# sheet0.net
KiCad netlist of a schematic drawn in Altium Designer
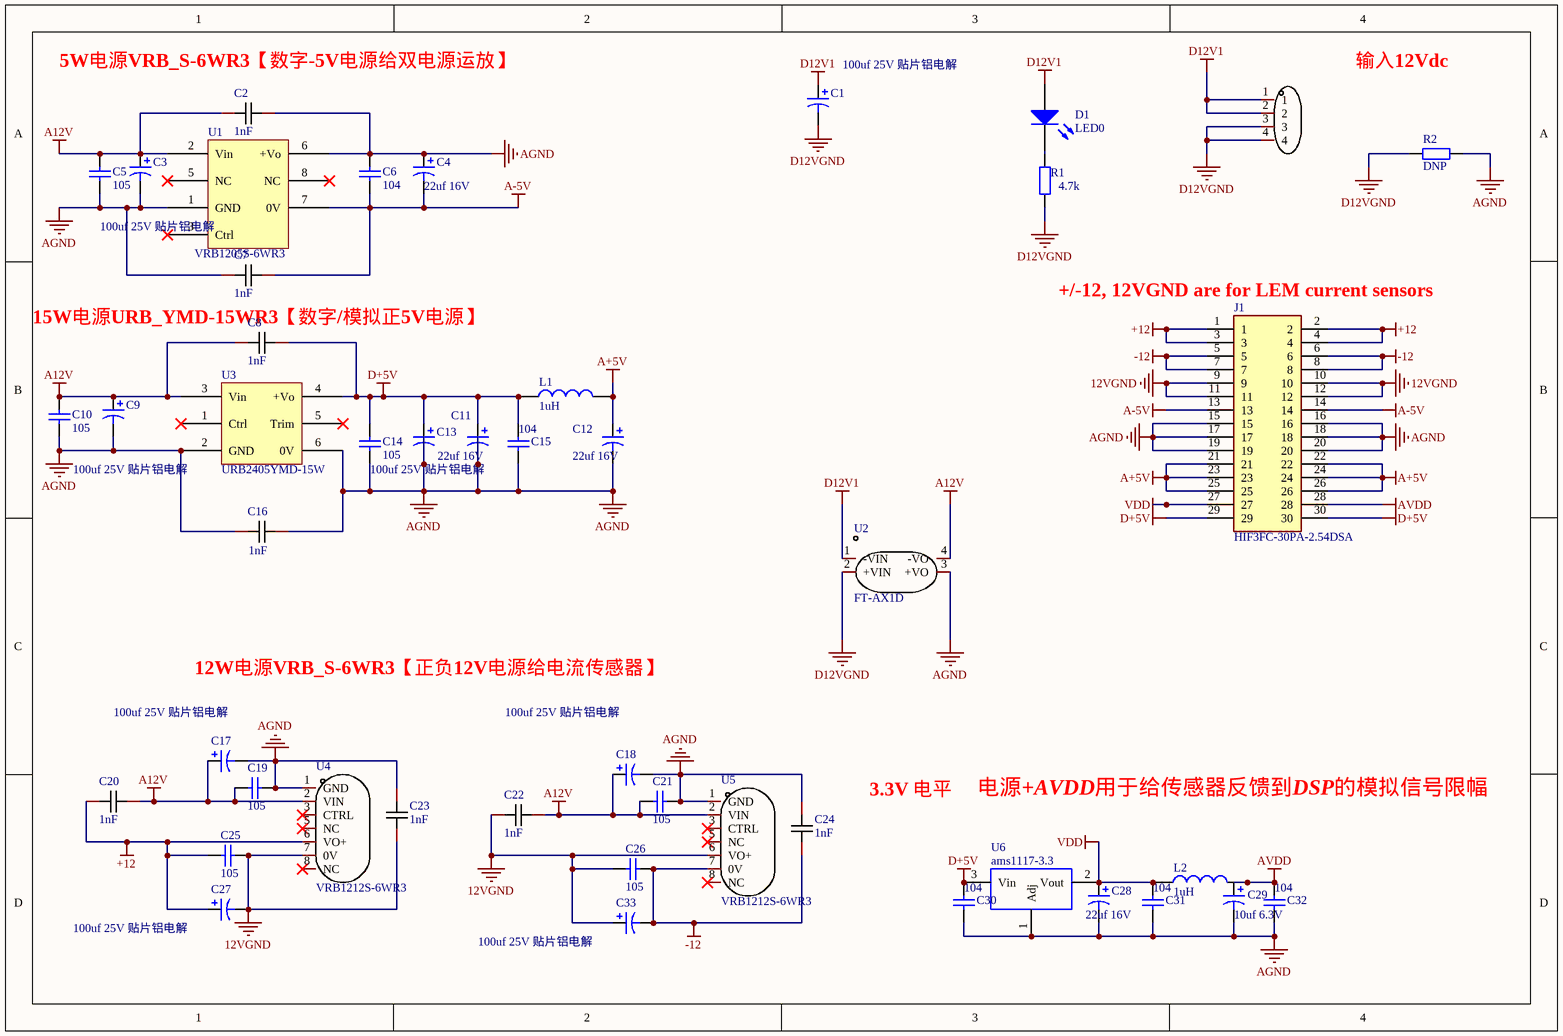
[diagram p0: sheet0.SchDoc]

(export (version "E")
  (design (tool "Eeschema 10.0.6"))
  (components
    (comp (ref "C1")
      (value "100uf 25V 贴片铝电解")
      (footprint "CAP/6.4mm -")
      (description "Polarized Capacitor (Radial)")
      (fields (field (name "PUBLISHER") "Altium Limited"))
      (libsource (lib "Miscellaneous Devices") (part "Cap Pol1"))
    )
    (comp (ref "C2")
      (value "1nF")
      (footprint "CAP-TH_L7.5-W4.5-P10.00-D0.6")
      (description "等级:Y1;容值:1nF;精度:±20%;电压(AC):400V;")
      (fields
        (field (name "MANUFACTURER") "KNSCHA(科尼盛)")
        (field (name "MANUFACTURER PART") "KY1102M400VAC70Y10093")
        (field (name "NAME") "1nF")
      )
      (libsource (lib "Power") (part "KY1102M400VAC70Y10093"))
    )
    (comp (ref "C3")
      (value "100uf 25V 贴片铝电解")
      (footprint "CAP/6.4mm -")
      (description "Polarized Capacitor (Radial)")
      (fields (field (name "PUBLISHER") "Altium Limited"))
      (libsource (lib "Miscellaneous Devices") (part "Cap Pol1"))
    )
    (comp (ref "C4")
      (value "22uf 16V")
      (footprint "Project_Oshinoko:1206 (钽电容)")
      (description "Polarized Capacitor (Radial)")
      (fields (field (name "PUBLISHER") "Altium Limited"))
      (libsource (lib "Project_Oshinoko") (part "Cap Pol1"))
    )
    (comp (ref "C5")
      (value "105")
      (footprint "Project_Oshinoko:0805")
      (description "Capacitor")
      (fields (field (name "PUBLISHER") "Altium Limited"))
      (libsource (lib "Miscellaneous Devices") (part "Cap"))
    )
    (comp (ref "C6")
      (value "104")
      (footprint "0805")
      (description "Capacitor")
      (fields (field (name "PUBLISHER") "Altium Limited"))
      (libsource (lib "Miscellaneous Devices") (part "Cap"))
    )
    (comp (ref "C7")
      (value "1nF")
      (footprint "CAP-TH_L7.5-W4.5-P10.00-D0.6")
      (description "等级:Y1;容值:1nF;精度:±20%;电压(AC):400V;")
      (fields
        (field (name "MANUFACTURER") "KNSCHA(科尼盛)")
        (field (name "MANUFACTURER PART") "KY1102M400VAC70Y10093")
        (field (name "NAME") "1nF")
      )
      (libsource (lib "Power") (part "KY1102M400VAC70Y10093"))
    )
    (comp (ref "C8")
      (value "1nF")
      (footprint "CAP-TH_L7.5-W4.5-P10.00-D0.6")
      (description "等级:Y1;容值:1nF;精度:±20%;电压(AC):400V;")
      (fields
        (field (name "MANUFACTURER") "KNSCHA(科尼盛)")
        (field (name "MANUFACTURER PART") "KY1102M400VAC70Y10093")
        (field (name "NAME") "1nF")
      )
      (libsource (lib "Power") (part "KY1102M400VAC70Y10093"))
    )
    (comp (ref "C9")
      (value "100uf 25V 贴片铝电解")
      (footprint "CAP/6.4mm -")
      (description "Polarized Capacitor (Radial)")
      (fields (field (name "PUBLISHER") "Altium Limited"))
      (libsource (lib "Miscellaneous Devices") (part "Cap Pol1"))
    )
    (comp (ref "C10")
      (value "105")
      (footprint "0805")
      (description "Capacitor")
      (fields (field (name "PUBLISHER") "Altium Limited"))
      (libsource (lib "Miscellaneous Devices") (part "Cap"))
    )
    (comp (ref "C11")
      (value "22uf 16V")
      (footprint "Project_Oshinoko:1206 (钽电容)")
      (description "Polarized Capacitor (Radial)")
      (fields (field (name "PUBLISHER") "Altium Limited"))
      (libsource (lib "Project_Oshinoko") (part "Cap Pol1"))
    )
    (comp (ref "C12")
      (value "22uf 16V")
      (footprint "Project_Oshinoko:1206 (钽电容)")
      (description "Polarized Capacitor (Radial)")
      (fields (field (name "PUBLISHER") "Altium Limited"))
      (libsource (lib "Project_Oshinoko") (part "Cap Pol1"))
    )
    (comp (ref "C13")
      (value "100uf 25V 贴片铝电解")
      (footprint "Project_Oshinoko:CAP/6.4mm -")
      (description "Polarized Capacitor (Radial)")
      (fields (field (name "PUBLISHER") "Altium Limited"))
      (libsource (lib "Miscellaneous Devices") (part "Cap Pol1"))
    )
    (comp (ref "C14")
      (value "105")
      (footprint "Project_Oshinoko:0805")
      (description "Capacitor")
      (fields (field (name "PUBLISHER") "Altium Limited"))
      (libsource (lib "Miscellaneous Devices") (part "Cap"))
    )
    (comp (ref "C15")
      (value "104")
      (footprint "Project_Oshinoko:0805")
      (description "Capacitor (Semiconductor SIM Model)")
      (fields (field (name "PUBLISHER") "Altium Limited"))
      (libsource (lib "Miscellaneous Devices") (part "Cap Semi"))
    )
    (comp (ref "C16")
      (value "1nF")
      (footprint "Project_Oshinoko:CAP-TH_L7.5-W4.5-P10.00-D0.6")
      (description "等级:Y1;容值:1nF;精度:±20%;电压(AC):400V;")
      (fields
        (field (name "MANUFACTURER") "KNSCHA(科尼盛)")
        (field (name "MANUFACTURER PART") "KY1102M400VAC70Y10093")
        (field (name "NAME") "1nF")
      )
      (libsource (lib "Project_Oshinoko") (part "KY1102M400VAC70Y10093"))
    )
    (comp (ref "C17")
      (value "100uf 25V 贴片铝电解")
      (footprint "CAP/6.4mm -")
      (description "Polarized Capacitor (Radial)")
      (fields (field (name "PUBLISHER") "Altium Limited"))
      (libsource (lib "Miscellaneous Devices") (part "Cap Pol1"))
    )
    (comp (ref "C18")
      (value "100uf 25V 贴片铝电解")
      (footprint "CAP/6.4mm -")
      (description "Polarized Capacitor (Radial)")
      (fields (field (name "PUBLISHER") "Altium Limited"))
      (libsource (lib "Miscellaneous Devices") (part "Cap Pol1"))
    )
    (comp (ref "C19")
      (value "105")
      (footprint "0805")
      (description "Capacitor")
      (fields (field (name "PUBLISHER") "Altium Limited"))
      (libsource (lib "Miscellaneous Devices") (part "Cap"))
    )
    (comp (ref "C20")
      (value "1nF")
      (footprint "CAP-TH_L7.5-W4.5-P10.00-D0.6")
      (description "等级:Y1;容值:1nF;精度:±20%;电压(AC):400V;")
      (fields
        (field (name "MANUFACTURER") "KNSCHA(科尼盛)")
        (field (name "MANUFACTURER PART") "KY1102M400VAC70Y10093")
        (field (name "NAME") "1nF")
      )
      (libsource (lib "Power") (part "KY1102M400VAC70Y10093"))
    )
    (comp (ref "C21")
      (value "105")
      (footprint "0805")
      (description "Capacitor")
      (fields (field (name "PUBLISHER") "Altium Limited"))
      (libsource (lib "Miscellaneous Devices") (part "Cap"))
    )
    (comp (ref "C22")
      (value "1nF")
      (footprint "CAP-TH_L7.5-W4.5-P10.00-D0.6")
      (description "等级:Y1;容值:1nF;精度:±20%;电压(AC):400V;")
      (fields
        (field (name "MANUFACTURER") "KNSCHA(科尼盛)")
        (field (name "MANUFACTURER PART") "KY1102M400VAC70Y10093")
        (field (name "NAME") "1nF")
      )
      (libsource (lib "Power") (part "KY1102M400VAC70Y10093"))
    )
    (comp (ref "C23")
      (value "1nF")
      (footprint "CAP-TH_L7.5-W4.5-P10.00-D0.6")
      (description "等级:Y1;容值:1nF;精度:±20%;电压(AC):400V;")
      (fields
        (field (name "MANUFACTURER") "KNSCHA(科尼盛)")
        (field (name "MANUFACTURER PART") "KY1102M400VAC70Y10093")
        (field (name "NAME") "1nF")
      )
      (libsource (lib "Power") (part "KY1102M400VAC70Y10093"))
    )
    (comp (ref "C24")
      (value "1nF")
      (footprint "CAP-TH_L7.5-W4.5-P10.00-D0.6")
      (description "等级:Y1;容值:1nF;精度:±20%;电压(AC):400V;")
      (fields
        (field (name "MANUFACTURER") "KNSCHA(科尼盛)")
        (field (name "MANUFACTURER PART") "KY1102M400VAC70Y10093")
        (field (name "NAME") "1nF")
      )
      (libsource (lib "Power") (part "KY1102M400VAC70Y10093"))
    )
    (comp (ref "C25")
      (value "105")
      (footprint "0805")
      (description "Capacitor")
      (fields (field (name "PUBLISHER") "Altium Limited"))
      (libsource (lib "Miscellaneous Devices") (part "Cap"))
    )
    (comp (ref "C26")
      (value "105")
      (footprint "0805")
      (description "Capacitor")
      (fields (field (name "PUBLISHER") "Altium Limited"))
      (libsource (lib "Miscellaneous Devices") (part "Cap"))
    )
    (comp (ref "C27")
      (value "100uf 25V 贴片铝电解")
      (footprint "CAP/6.4mm -")
      (description "Polarized Capacitor (Radial)")
      (fields (field (name "PUBLISHER") "Altium Limited"))
      (libsource (lib "Miscellaneous Devices") (part "Cap Pol1"))
    )
    (comp (ref "C28")
      (value "22uf 16V")
      (footprint "Project_Oshinoko:1206 (钽电容)")
      (description "Polarized Capacitor (Radial)")
      (fields (field (name "PUBLISHER") "Altium Limited"))
      (libsource (lib "Project_Oshinoko") (part "Cap Pol1"))
    )
    (comp (ref "C29")
      (value "10uf 6.3V")
      (footprint "Project_Oshinoko:1206 (钽电容)")
      (description "Polarized Capacitor (Radial)")
      (fields (field (name "PUBLISHER") "Altium Limited"))
      (libsource (lib "Project_Oshinoko") (part "Cap Pol1"))
    )
    (comp (ref "C30")
      (value "104")
      (footprint "0805")
      (description "Capacitor (Semiconductor SIM Model)")
      (fields (field (name "PUBLISHER") "Altium Limited"))
      (libsource (lib "Miscellaneous Devices") (part "Cap Semi"))
    )
    (comp (ref "C31")
      (value "104")
      (footprint "0805")
      (description "Capacitor (Semiconductor SIM Model)")
      (fields (field (name "PUBLISHER") "Altium Limited"))
      (libsource (lib "Miscellaneous Devices") (part "Cap Semi"))
    )
    (comp (ref "C32")
      (value "104")
      (footprint "0805")
      (description "Capacitor (Semiconductor SIM Model)")
      (fields (field (name "PUBLISHER") "Altium Limited"))
      (libsource (lib "Project_Oshinoko") (part "Cap Semi"))
    )
    (comp (ref "C33")
      (value "100uf 25V 贴片铝电解")
      (footprint "CAP/6.4mm -")
      (description "Polarized Capacitor (Radial)")
      (fields (field (name "PUBLISHER") "Altium Limited"))
      (libsource (lib "Miscellaneous Devices") (part "Cap Pol1"))
    )
    (comp (ref "CN1")
      (value "DB2EVC-3.81-4P-GN")
      (footprint "CONN-TH_4P-P3.81_DB2EVC-3.81-4P")
      (fields (field (name "MANUFACTURER") "DIBO(地博电气)"))
      (libsource (lib "Project_Oshinoko") (part "DB2EVC-3.81-4P-GN"))
    )
    (comp (ref "D1")
      (value "LED0")
      (footprint "l0805")
      (description "Typical INFRARED GaAs LED")
      (fields (field (name "PUBLISHER") "Altium Limited"))
      (libsource (lib "Miscellaneous Devices") (part "LED0"))
    )
    (comp (ref "J1")
      (value "HIF3FC-30PA-2.54DSA")
      (footprint "HDR2.54-LI-2x15P")
      (description "Connector")
      (fields
        (field (name "MANUFACTURER_PART_NUMBER") "HIF3FC-30PA-2.54DSA(71)")
        (field (name "MOUSER PART NUMBER") "798-HIF3FC30PA254D71")
      )
      (libsource (lib "Project_Arsene") (part "HIF3FC-30PA-2.54DSA"))
    )
    (comp (ref "L1")
      (value "1uH")
      (footprint "L 0805")
      (description "小功率贴片电感")
      (fields (field (name "版权归属") "源创客"))
      (libsource (lib "3.1   - 电阻-电容-电感") (part "L"))
    )
    (comp (ref "L2")
      (value "1uH")
      (footprint "L 0805")
      (description "小功率贴片电感")
      (fields (field (name "版权归属") "源创客"))
      (libsource (lib "3.1   - 电阻-电容-电感") (part "L"))
    )
    (comp (ref "R1")
      (value "4.7k")
      (footprint "0805")
      (description "Resistor")
      (fields (field (name "PUBLISHER") "Altium Limited"))
      (libsource (lib "Project_Oshinoko") (part "Res2"))
    )
    (comp (ref "R2")
      (value "DNP")
      (footprint "Project_Oshinoko:2512")
      (description "Resistor")
      (fields (field (name "PUBLISHER") "Altium Limited"))
      (libsource (lib "") (part "Res2_1"))
    )
    (comp (ref "U1")
      (value "VRB1205S-6WR3")
      (footprint "Project_Oshinoko:VRB_S-6WR3")
      (libsource (lib "") (part "Component_1_1"))
    )
    (comp (ref "U2")
      (value "FT-AX1D")
      (footprint "Project_Oshinoko:PWRM-TH_MORNSUN_FT-AX1D")
      (fields (field (name "MANUFACTURER") "MORNSUN(金升阳)") (field (name "NAME") "FT-AX1D"))
      (libsource (lib "Project_Oshinoko") (part "FT-AX1D"))
    )
    (comp (ref "U3")
      (value "URB2405YMD-15W")
      (footprint "Project_Oshinoko:URB-YMD-15WR3")
      (libsource (lib "Schlib1") (part "Component_1"))
    )
    (comp (ref "U4")
      (value "VRB1212S-6WR3")
      (footprint "PWRM-TH_VRB2405S-6WR3")
      (description "输入电压(DC):9V~18V;输出电压:12V;输出电流(最大值):500mA;输出功率:6W;转换效率:84%;")
      (fields (field (name "NAME") "VRB1212S-6WR3") (field (name "MANUFACTURER") "MORNSUN(金升阳)"))
      (libsource (lib "Power_Lib") (part "VRB1212S-6WR3"))
    )
    (comp (ref "U5")
      (value "VRB1212S-6WR3")
      (footprint "PWRM-TH_VRB2405S-6WR3")
      (description "输入电压(DC):9V~18V;输出电压:12V;输出电流(最大值):500mA;输出功率:6W;转换效率:84%;")
      (fields (field (name "NAME") "VRB1212S-6WR3") (field (name "MANUFACTURER") "MORNSUN(金升阳)"))
      (libsource (lib "Power_Lib") (part "VRB1212S-6WR3"))
    )
    (comp (ref "U6")
      (value "ams1117-3.3")
      (footprint "SOT-223")
      (libsource (lib "myself-schlib") (part "LM1117"))
    )
  )
  (nets
    (net (code "1") (name "+12") (class "Default")
      (node (ref "C20") (pin "2") (pinfunction "2_2") (pintype "passive"))
      (node (ref "C25") (pin "1") (pinfunction "1_1") (pintype "passive"))
      (node (ref "C27") (pin "1") (pinfunction "1_1") (pintype "passive"))
      (node (ref "J1") (pin "1") (pinfunction "1_1") (pintype "passive"))
      (node (ref "J1") (pin "2") (pinfunction "2_2") (pintype "passive"))
      (node (ref "J1") (pin "3") (pinfunction "3_3") (pintype "passive"))
      (node (ref "J1") (pin "4") (pinfunction "4_4") (pintype "passive"))
      (node (ref "U4") (pin "6") (pinfunction "VO+_6") (pintype "passive"))
    )
    (net (code "2") (name "-12") (class "Default")
      (node (ref "C24") (pin "2") (pinfunction "2_2") (pintype "passive"))
      (node (ref "C26") (pin "2") (pinfunction "2_2") (pintype "passive"))
      (node (ref "C33") (pin "2") (pinfunction "2_2") (pintype "passive"))
      (node (ref "J1") (pin "5") (pinfunction "5_5") (pintype "passive"))
      (node (ref "J1") (pin "6") (pinfunction "6_6") (pintype "passive"))
      (node (ref "J1") (pin "7") (pinfunction "7_7") (pintype "passive"))
      (node (ref "J1") (pin "8") (pinfunction "8_8") (pintype "passive"))
      (node (ref "U5") (pin "7") (pinfunction "0V_7") (pintype "passive"))
    )
    (net (code "3") (name "12VGND") (class "Default")
      (node (ref "C22") (pin "2") (pinfunction "2_2") (pintype "passive"))
      (node (ref "C23") (pin "2") (pinfunction "2_2") (pintype "passive"))
      (node (ref "C25") (pin "2") (pinfunction "2_2") (pintype "passive"))
      (node (ref "C26") (pin "1") (pinfunction "1_1") (pintype "passive"))
      (node (ref "C27") (pin "2") (pinfunction "2_2") (pintype "passive"))
      (node (ref "C33") (pin "1") (pinfunction "1_1") (pintype "passive"))
      (node (ref "J1") (pin "10") (pinfunction "10_10") (pintype "passive"))
      (node (ref "J1") (pin "11") (pinfunction "11_11") (pintype "passive"))
      (node (ref "J1") (pin "12") (pinfunction "12_12") (pintype "passive"))
      (node (ref "J1") (pin "9") (pinfunction "9_9") (pintype "passive"))
      (node (ref "U4") (pin "7") (pinfunction "0V_7") (pintype "passive"))
      (node (ref "U5") (pin "6") (pinfunction "VO+_6") (pintype "passive"))
    )
    (net (code "4") (name "A+5V") (class "Default")
      (node (ref "C12") (pin "1") (pinfunction "1_1") (pintype "passive"))
      (node (ref "J1") (pin "21") (pinfunction "21_21") (pintype "passive"))
      (node (ref "J1") (pin "22") (pinfunction "22_22") (pintype "passive"))
      (node (ref "J1") (pin "23") (pinfunction "23_23") (pintype "passive"))
      (node (ref "J1") (pin "24") (pinfunction "24_24") (pintype "passive"))
      (node (ref "J1") (pin "25") (pinfunction "25_25") (pintype "passive"))
      (node (ref "J1") (pin "26") (pinfunction "26_26") (pintype "passive"))
      (node (ref "L1") (pin "2") (pinfunction "2_2") (pintype "passive"))
    )
    (net (code "5") (name "A-5V") (class "Default")
      (node (ref "C4") (pin "2") (pinfunction "2_2") (pintype "passive"))
      (node (ref "C6") (pin "2") (pinfunction "2_2") (pintype "passive"))
      (node (ref "C7") (pin "2") (pinfunction "2_2") (pintype "passive"))
      (node (ref "J1") (pin "13") (pinfunction "13_13") (pintype "passive"))
      (node (ref "J1") (pin "14") (pinfunction "14_14") (pintype "passive"))
      (node (ref "U1") (pin "7") (pinfunction "0V_7") (pintype "passive"))
    )
    (net (code "6") (name "A12V") (class "Default")
      (node (ref "C10") (pin "1") (pinfunction "1_1") (pintype "passive"))
      (node (ref "C17") (pin "1") (pinfunction "1_1") (pintype "passive"))
      (node (ref "C18") (pin "1") (pinfunction "1_1") (pintype "passive"))
      (node (ref "C19") (pin "1") (pinfunction "1_1") (pintype "passive"))
      (node (ref "C2") (pin "1") (pinfunction "1_1") (pintype "passive"))
      (node (ref "C20") (pin "1") (pinfunction "1_1") (pintype "passive"))
      (node (ref "C21") (pin "1") (pinfunction "1_1") (pintype "passive"))
      (node (ref "C22") (pin "1") (pinfunction "1_1") (pintype "passive"))
      (node (ref "C3") (pin "1") (pinfunction "1_1") (pintype "passive"))
      (node (ref "C5") (pin "1") (pinfunction "1_1") (pintype "passive"))
      (node (ref "C8") (pin "1") (pinfunction "1_1") (pintype "passive"))
      (node (ref "C9") (pin "1") (pinfunction "1_1") (pintype "passive"))
      (node (ref "U1") (pin "2") (pinfunction "Vin_2") (pintype "passive"))
      (node (ref "U2") (pin "4") (pinfunction "-VO_4") (pintype "passive"))
      (node (ref "U3") (pin "3") (pinfunction "Vin_3") (pintype "passive"))
      (node (ref "U4") (pin "2") (pinfunction "VIN_2") (pintype "passive"))
      (node (ref "U5") (pin "2") (pinfunction "VIN_2") (pintype "passive"))
    )
    (net (code "7") (name "AGND") (class "Default")
      (node (ref "C10") (pin "2") (pinfunction "2_2") (pintype "passive"))
      (node (ref "C11") (pin "2") (pinfunction "2_2") (pintype "passive"))
      (node (ref "C12") (pin "2") (pinfunction "2_2") (pintype "passive"))
      (node (ref "C13") (pin "2") (pinfunction "2_2") (pintype "passive"))
      (node (ref "C14") (pin "2") (pinfunction "2_2") (pintype "passive"))
      (node (ref "C15") (pin "1") (pinfunction "1_1") (pintype "passive"))
      (node (ref "C16") (pin "1") (pinfunction "1_1") (pintype "passive"))
      (node (ref "C16") (pin "2") (pinfunction "2_2") (pintype "passive"))
      (node (ref "C17") (pin "2") (pinfunction "2_2") (pintype "passive"))
      (node (ref "C18") (pin "2") (pinfunction "2_2") (pintype "passive"))
      (node (ref "C19") (pin "2") (pinfunction "2_2") (pintype "passive"))
      (node (ref "C2") (pin "2") (pinfunction "2_2") (pintype "passive"))
      (node (ref "C21") (pin "2") (pinfunction "2_2") (pintype "passive"))
      (node (ref "C23") (pin "1") (pinfunction "1_1") (pintype "passive"))
      (node (ref "C24") (pin "1") (pinfunction "1_1") (pintype "passive"))
      (node (ref "C28") (pin "2") (pinfunction "2_2") (pintype "passive"))
      (node (ref "C29") (pin "2") (pinfunction "2_2") (pintype "passive"))
      (node (ref "C3") (pin "2") (pinfunction "2_2") (pintype "passive"))
      (node (ref "C30") (pin "1") (pinfunction "1_1") (pintype "passive"))
      (node (ref "C31") (pin "1") (pinfunction "1_1") (pintype "passive"))
      (node (ref "C32") (pin "1") (pinfunction "1_1") (pintype "passive"))
      (node (ref "C4") (pin "1") (pinfunction "1_1") (pintype "passive"))
      (node (ref "C5") (pin "2") (pinfunction "2_2") (pintype "passive"))
      (node (ref "C6") (pin "1") (pinfunction "1_1") (pintype "passive"))
      (node (ref "C7") (pin "1") (pinfunction "1_1") (pintype "passive"))
      (node (ref "C9") (pin "2") (pinfunction "2_2") (pintype "passive"))
      (node (ref "J1") (pin "15") (pinfunction "15_15") (pintype "passive"))
      (node (ref "J1") (pin "16") (pinfunction "16_16") (pintype "passive"))
      (node (ref "J1") (pin "17") (pinfunction "17_17") (pintype "passive"))
      (node (ref "J1") (pin "18") (pinfunction "18_18") (pintype "passive"))
      (node (ref "J1") (pin "19") (pinfunction "19_19") (pintype "passive"))
      (node (ref "J1") (pin "20") (pinfunction "20_20") (pintype "passive"))
      (node (ref "R2") (pin "2") (pinfunction "2_2") (pintype "passive"))
      (node (ref "U1") (pin "1") (pinfunction "GND_1") (pintype "passive"))
      (node (ref "U1") (pin "6") (pinfunction "+Vo_6") (pintype "passive"))
      (node (ref "U2") (pin "3") (pinfunction "+VO_3") (pintype "passive"))
      (node (ref "U3") (pin "2") (pinfunction "GND_2") (pintype "passive"))
      (node (ref "U3") (pin "6") (pinfunction "0V_6") (pintype "passive"))
      (node (ref "U4") (pin "1") (pinfunction "GND_1") (pintype "passive"))
      (node (ref "U5") (pin "1") (pinfunction "GND_1") (pintype "passive"))
      (node (ref "U6") (pin "1") (pinfunction "Adj_1") (pintype "passive"))
    )
    (net (code "8") (name "AVDD") (class "Default")
      (node (ref "C29") (pin "1") (pinfunction "1_1") (pintype "passive"))
      (node (ref "C32") (pin "2") (pinfunction "2_2") (pintype "passive"))
      (node (ref "J1") (pin "28") (pinfunction "28_28") (pintype "passive"))
      (node (ref "L2") (pin "2") (pinfunction "2_2") (pintype "passive"))
    )
    (net (code "9") (name "D+5V") (class "Default")
      (node (ref "C11") (pin "1") (pinfunction "1_1") (pintype "passive"))
      (node (ref "C13") (pin "1") (pinfunction "1_1") (pintype "passive"))
      (node (ref "C14") (pin "1") (pinfunction "1_1") (pintype "passive"))
      (node (ref "C15") (pin "2") (pinfunction "2_2") (pintype "passive"))
      (node (ref "C30") (pin "2") (pinfunction "2_2") (pintype "passive"))
      (node (ref "C8") (pin "2") (pinfunction "2_2") (pintype "passive"))
      (node (ref "J1") (pin "29") (pinfunction "29_29") (pintype "passive"))
      (node (ref "J1") (pin "30") (pinfunction "30_30") (pintype "passive"))
      (node (ref "L1") (pin "1") (pinfunction "1_1") (pintype "passive"))
      (node (ref "U3") (pin "4") (pinfunction "+Vo_4") (pintype "passive"))
      (node (ref "U6") (pin "3") (pinfunction "Vin_3") (pintype "passive"))
    )
    (net (code "10") (name "D12V1") (class "Default")
      (node (ref "C1") (pin "1") (pinfunction "1_1") (pintype "passive"))
      (node (ref "CN1") (pin "1") (pinfunction "1_1") (pintype "passive"))
      (node (ref "CN1") (pin "2") (pinfunction "2_2") (pintype "passive"))
      (node (ref "D1") (pin "1") (pinfunction "A_1") (pintype "passive"))
      (node (ref "U2") (pin "1") (pinfunction "-VIN_1") (pintype "passive"))
    )
    (net (code "11") (name "D12VGND") (class "Default")
      (node (ref "C1") (pin "2") (pinfunction "2_2") (pintype "passive"))
      (node (ref "CN1") (pin "3") (pinfunction "3_3") (pintype "passive"))
      (node (ref "CN1") (pin "4") (pinfunction "4_4") (pintype "passive"))
      (node (ref "R1") (pin "1") (pinfunction "1_1") (pintype "passive"))
      (node (ref "R2") (pin "1") (pinfunction "1_1") (pintype "passive"))
      (node (ref "U2") (pin "2") (pinfunction "+VIN_2") (pintype "passive"))
    )
    (net (code "12") (name "Net-(D1-K)") (class "Default")
      (node (ref "D1") (pin "2") (pinfunction "K_2") (pintype "passive"))
      (node (ref "R1") (pin "2") (pinfunction "2_2") (pintype "passive"))
    )
    (net (code "13") (name "VDD") (class "Default")
      (node (ref "C28") (pin "1") (pinfunction "1_1") (pintype "passive"))
      (node (ref "C31") (pin "2") (pinfunction "2_2") (pintype "passive"))
      (node (ref "J1") (pin "27") (pinfunction "27_27") (pintype "passive"))
      (node (ref "L2") (pin "1") (pinfunction "1_1") (pintype "passive"))
      (node (ref "U6") (pin "2") (pinfunction "Vout_2") (pintype "passive"))
    )
    (net (code "14") (name "unconnected-(U1-Ctrl-Pad3)") (class "Default")
      (node (ref "U1") (pin "3") (pinfunction "Ctrl_3") (pintype "passive+no_connect"))
    )
    (net (code "15") (name "unconnected-(U1-NC-Pad5)") (class "Default")
      (node (ref "U1") (pin "5") (pinfunction "NC_5") (pintype "passive+no_connect"))
    )
    (net (code "16") (name "unconnected-(U1-NC-Pad8)") (class "Default")
      (node (ref "U1") (pin "8") (pinfunction "NC_8") (pintype "passive+no_connect"))
    )
    (net (code "17") (name "unconnected-(U3-Ctrl-Pad1)") (class "Default")
      (node (ref "U3") (pin "1") (pinfunction "Ctrl_1") (pintype "passive+no_connect"))
    )
    (net (code "18") (name "unconnected-(U3-Trim-Pad5)") (class "Default")
      (node (ref "U3") (pin "5") (pinfunction "Trim_5") (pintype "passive+no_connect"))
    )
    (net (code "19") (name "unconnected-(U4-CTRL-Pad3)") (class "Default")
      (node (ref "U4") (pin "3") (pinfunction "CTRL_3") (pintype "passive+no_connect"))
    )
    (net (code "20") (name "unconnected-(U4-NC-Pad5)") (class "Default")
      (node (ref "U4") (pin "5") (pinfunction "NC_5") (pintype "passive+no_connect"))
    )
    (net (code "21") (name "unconnected-(U4-NC-Pad8)") (class "Default")
      (node (ref "U4") (pin "8") (pinfunction "NC_8") (pintype "passive+no_connect"))
    )
    (net (code "22") (name "unconnected-(U5-CTRL-Pad3)") (class "Default")
      (node (ref "U5") (pin "3") (pinfunction "CTRL_3") (pintype "passive+no_connect"))
    )
    (net (code "23") (name "unconnected-(U5-NC-Pad5)") (class "Default")
      (node (ref "U5") (pin "5") (pinfunction "NC_5") (pintype "passive+no_connect"))
    )
    (net (code "24") (name "unconnected-(U5-NC-Pad8)") (class "Default")
      (node (ref "U5") (pin "8") (pinfunction "NC_8") (pintype "passive+no_connect"))
    )
  )
)
